# AutoReverseAVR2.net
KiCad netlist of a schematic drawn in Altium Designer
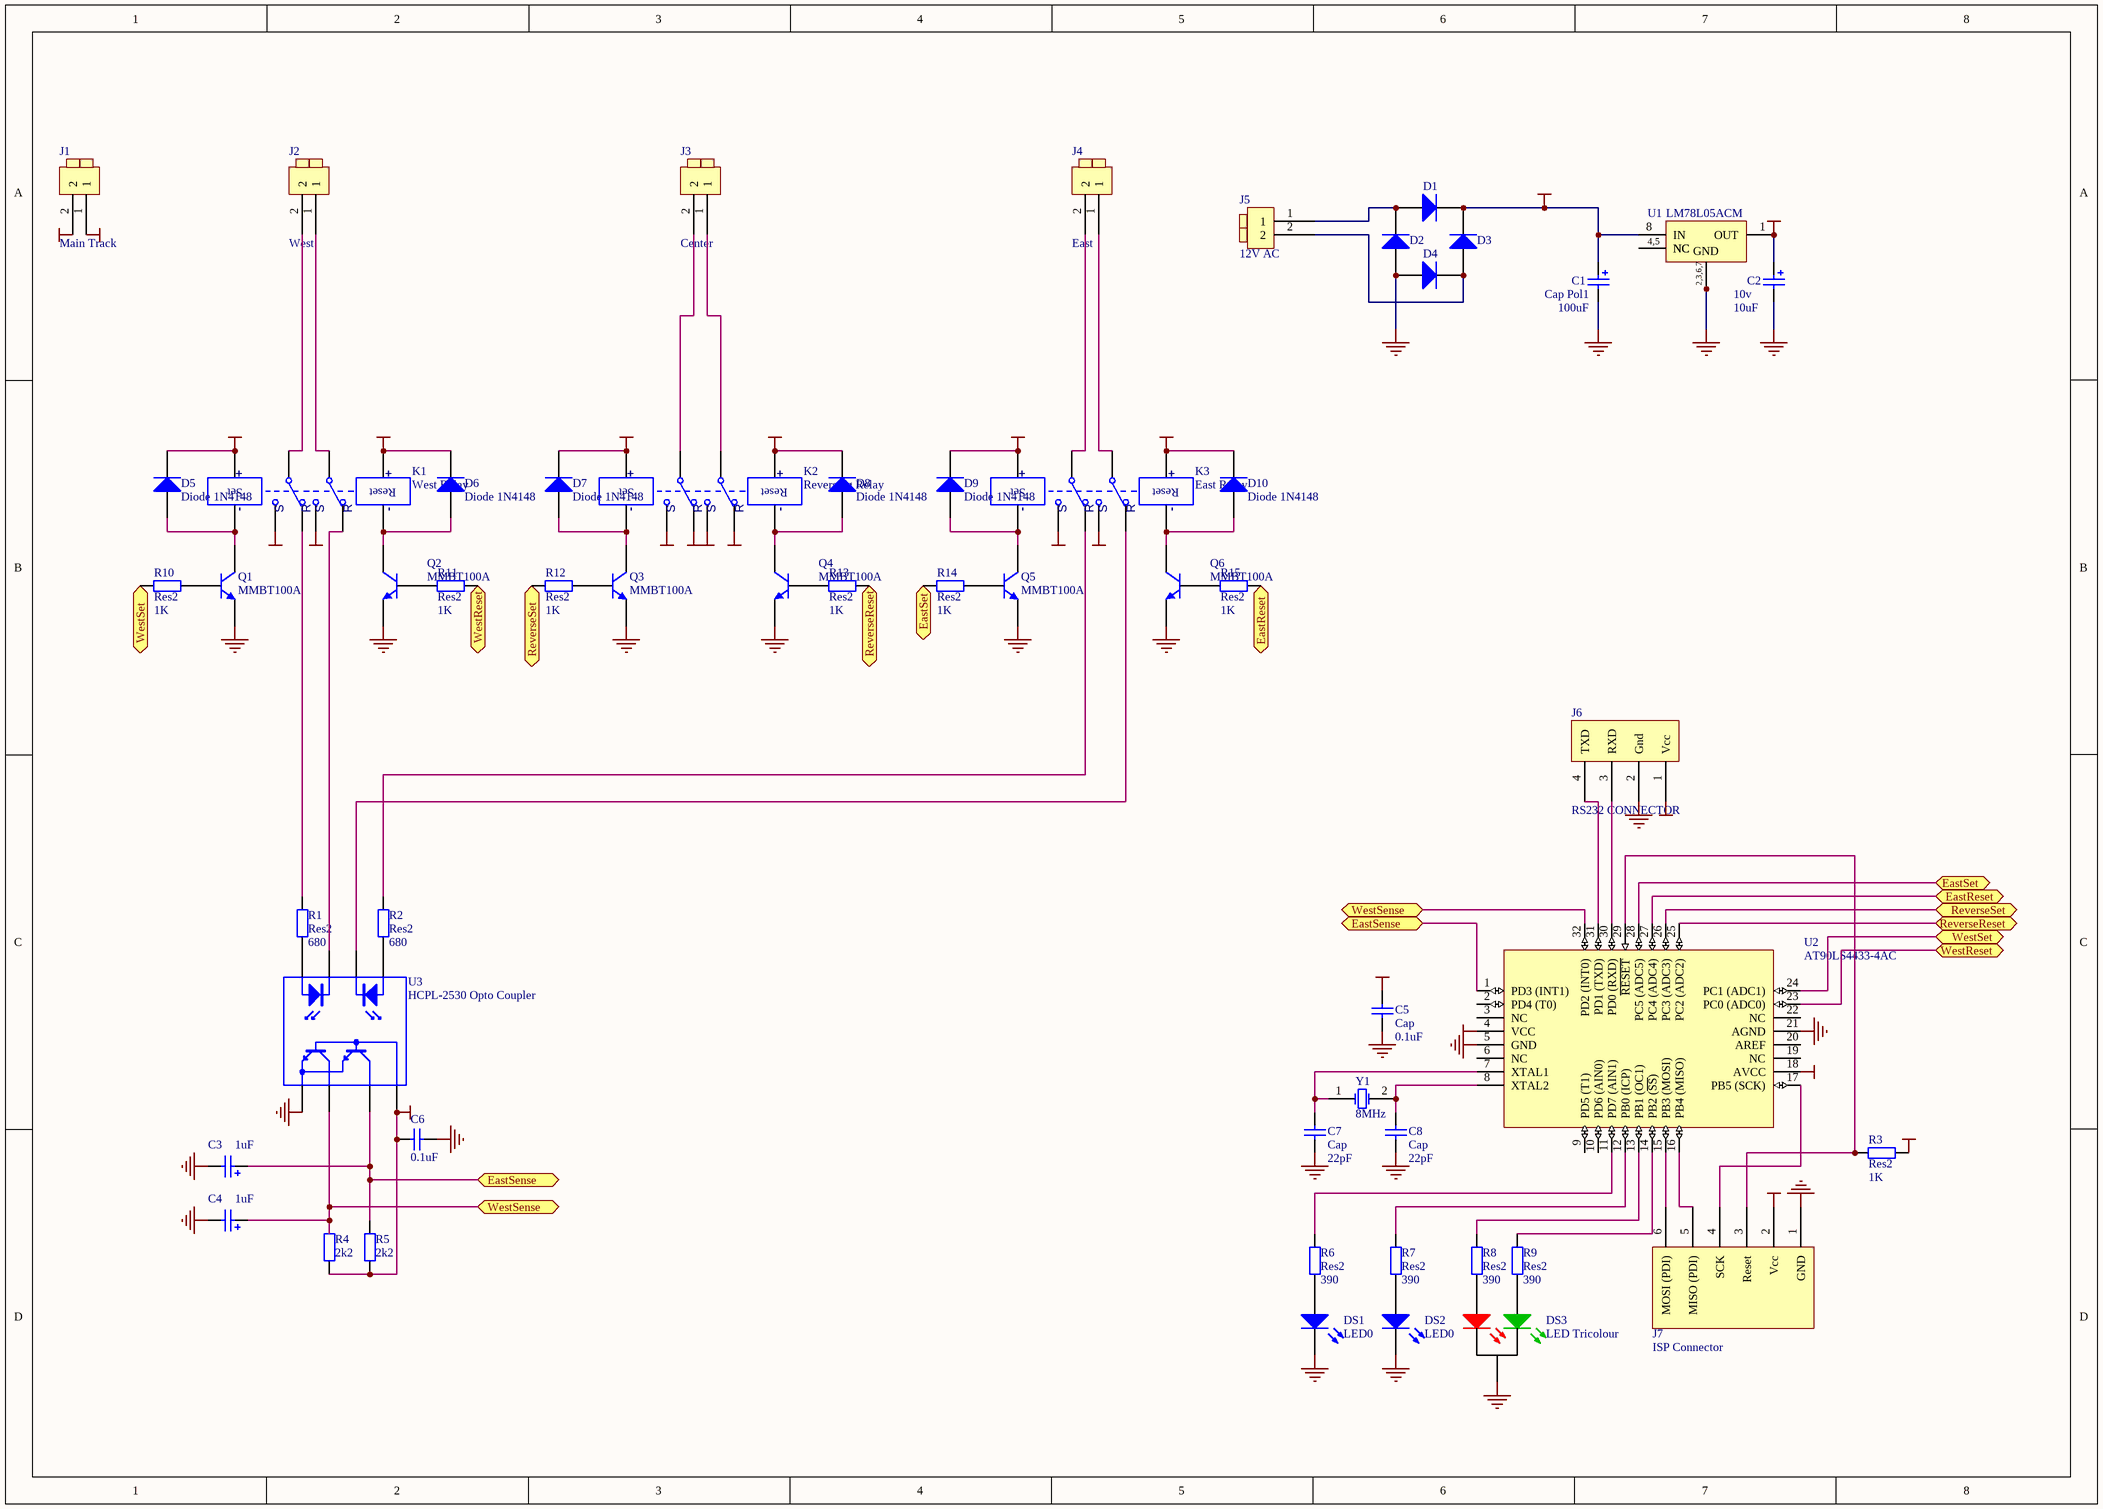
[diagram p0: AutoReverseAVR2.SchDoc]

(export (version "E")
  (design (tool "Eeschema 10.0.6"))
  (components
    (comp (ref "C1")
      (value "Cap Pol1")
      (footprint "CAPPR5-10X10.5")
      (description "Polarized Capacitor (Radial)")
      (fields (field (name "ALTIUM_VALUE") "100uF") (field (name "PUBLISHER") "Altium Limited"))
      (libsource (lib "Miscellaneous Devices") (part "Cap Pol1"))
    )
    (comp (ref "C2")
      (value "10v")
      (footprint "CC3216-1206")
      (description "Polarized Capacitor (Radial)")
      (fields (field (name "ALTIUM_VALUE") "10uF") (field (name "PUBLISHER") "Altium Limited"))
      (libsource (lib "Miscellaneous Devices") (part "Cap Pol1"))
    )
    (comp (ref "C3")
      (value "1uF")
      (footprint "CC3216-1206")
      (description "Polarized Capacitor (Radial)")
      (fields (field (name "Comment") "Cap Pol1") (field (name "PUBLISHER") "Altium Limited"))
      (libsource (lib "Miscellaneous Devices") (part "Cap Pol1"))
    )
    (comp (ref "C4")
      (value "1uF")
      (footprint "CC3216-1206")
      (description "Polarized Capacitor (Radial)")
      (fields (field (name "Comment") "Cap Pol1") (field (name "PUBLISHER") "Altium Limited"))
      (libsource (lib "Miscellaneous Devices") (part "Cap Pol1"))
    )
    (comp (ref "C5")
      (value "Cap")
      (footprint "CC2012-0805")
      (description "Capacitor")
      (fields (field (name "ALTIUM_VALUE") "0.1uF") (field (name "PUBLISHER") "Altium Limited"))
      (libsource (lib "Miscellaneous Devices") (part "Cap"))
    )
    (comp (ref "C6")
      (value "0.1uF")
      (footprint "CC2012-0805")
      (description "Capacitor")
      (fields (field (name "Comment") "Cap") (field (name "PUBLISHER") "Altium Limited"))
      (libsource (lib "Miscellaneous Devices") (part "Cap"))
    )
    (comp (ref "C7")
      (value "Cap")
      (footprint "CC2012-0805")
      (description "Capacitor")
      (fields (field (name "ALTIUM_VALUE") "22pF") (field (name "PUBLISHER") "Altium Limited"))
      (libsource (lib "Miscellaneous Devices") (part "Cap"))
    )
    (comp (ref "C8")
      (value "Cap")
      (footprint "CC2012-0805")
      (description "Capacitor")
      (fields (field (name "ALTIUM_VALUE") "22pF") (field (name "PUBLISHER") "Altium Limited"))
      (libsource (lib "Miscellaneous Devices") (part "Cap"))
    )
    (comp (ref "D1")
      (value "Diode 1N4004")
      (footprint "DIO10.46-5.3x2.8")
      (description "1 Amp General Purpose Rectifier")
      (fields (field (name "PUBLISHER") "Altium Limited"))
      (libsource (lib "Miscellaneous Devices") (part "Diode 1N4004"))
    )
    (comp (ref "D2")
      (value "Diode 1N4004")
      (footprint "DIO10.46-5.3x2.8")
      (description "1 Amp General Purpose Rectifier")
      (fields (field (name "PUBLISHER") "Altium Limited"))
      (libsource (lib "Miscellaneous Devices") (part "Diode 1N4004"))
    )
    (comp (ref "D3")
      (value "Diode 1N4004")
      (footprint "DIO10.46-5.3x2.8")
      (description "1 Amp General Purpose Rectifier")
      (fields (field (name "PUBLISHER") "Altium Limited"))
      (libsource (lib "Miscellaneous Devices") (part "Diode 1N4004"))
    )
    (comp (ref "D4")
      (value "Diode 1N4004")
      (footprint "DIO10.46-5.3x2.8")
      (description "1 Amp General Purpose Rectifier")
      (fields (field (name "PUBLISHER") "Altium Limited"))
      (libsource (lib "Miscellaneous Devices") (part "Diode 1N4004"))
    )
    (comp (ref "D5")
      (value "Diode 1N4148")
      (footprint "DIO7.1-3.9x1.9")
      (description "High Conductance Fast Diode")
      (fields (field (name "PUBLISHER") "Altium Limited"))
      (libsource (lib "Miscellaneous Devices") (part "Diode 1N4148"))
    )
    (comp (ref "D6")
      (value "Diode 1N4148")
      (footprint "DIO7.1-3.9x1.9")
      (description "High Conductance Fast Diode")
      (fields (field (name "PUBLISHER") "Altium Limited"))
      (libsource (lib "Miscellaneous Devices") (part "Diode 1N4148"))
    )
    (comp (ref "D7")
      (value "Diode 1N4148")
      (footprint "DIO7.1-3.9x1.9")
      (description "High Conductance Fast Diode")
      (fields (field (name "PUBLISHER") "Altium Limited"))
      (libsource (lib "Miscellaneous Devices") (part "Diode 1N4148"))
    )
    (comp (ref "D8")
      (value "Diode 1N4148")
      (footprint "DIO7.1-3.9x1.9")
      (description "High Conductance Fast Diode")
      (fields (field (name "PUBLISHER") "Altium Limited"))
      (libsource (lib "Miscellaneous Devices") (part "Diode 1N4148"))
    )
    (comp (ref "D9")
      (value "Diode 1N4148")
      (footprint "DIO7.1-3.9x1.9")
      (description "High Conductance Fast Diode")
      (fields (field (name "PUBLISHER") "Altium Limited"))
      (libsource (lib "Miscellaneous Devices") (part "Diode 1N4148"))
    )
    (comp (ref "D10")
      (value "Diode 1N4148")
      (footprint "DIO7.1-3.9x1.9")
      (description "High Conductance Fast Diode")
      (fields (field (name "PUBLISHER") "Altium Limited"))
      (libsource (lib "Miscellaneous Devices") (part "Diode 1N4148"))
    )
    (comp (ref "DS1")
      (value "LED0")
      (footprint "LED3mm")
      (description "Typical INFRARED GaAs LED")
      (fields (field (name "PUBLISHER") "Altium Limited"))
      (libsource (lib "Miscellaneous Devices") (part "LED0"))
    )
    (comp (ref "DS2")
      (value "LED0")
      (footprint "LED3mm")
      (description "Typical INFRARED GaAs LED")
      (fields (field (name "PUBLISHER") "Altium Limited"))
      (libsource (lib "Miscellaneous Devices") (part "LED0"))
    )
    (comp (ref "DS3")
      (value "LED Tricolour")
      (footprint "LED3mm TriColour")
      (description "Typical Red Green Tri Color LED")
      (fields (field (name "PUBLISHER") "Altium Limited"))
      (libsource (lib "Custom") (part "LED Tricolour"))
    )
    (comp (ref "J1")
      (value "Main Track")
      (footprint "Screw Terminal 2 way 0.2")
      (libsource (lib "Custom") (part "Screw Terminal 2 Way"))
    )
    (comp (ref "J2")
      (value "West")
      (footprint "Screw Terminal 2 way 0.2")
      (libsource (lib "Custom") (part "Screw Terminal 2 Way"))
    )
    (comp (ref "J3")
      (value "Center")
      (footprint "Screw Terminal 2 way 0.2")
      (libsource (lib "Custom") (part "Screw Terminal 2 Way"))
    )
    (comp (ref "J4")
      (value "East")
      (footprint "Screw Terminal 2 way 0.2")
      (libsource (lib "Custom") (part "Screw Terminal 2 Way"))
    )
    (comp (ref "J5")
      (value "12V AC")
      (footprint "Screw Terminal 2 way 0.2")
      (libsource (lib "") (part "Screw Terminal 2 Way_1"))
    )
    (comp (ref "J6")
      (value "RS232 CONNECTOR")
      (footprint "0.1 SIP 4 PIN")
      (libsource (lib "Custom") (part "RS232 CONNECTOR"))
    )
    (comp (ref "J7")
      (value "ISP Connector")
      (footprint "0.1 SIP 6 PIN")
      (libsource (lib "Custom") (part "ISP Connector"))
    )
    (comp (ref "K1")
      (value "West Relay")
      (footprint "DIP-10")
      (description "EA2-5T Dual Coil 5V Latching Relay")
      (fields (field (name "PUBLISHER") "Altium Limited"))
      (libsource (lib "Custom") (part "EA2-5T Dual Coil 5V Latching Relay"))
    )
    (comp (ref "K2")
      (value "Reversing Relay")
      (footprint "DIP-10")
      (description "EA2-5T Dual Coil 5V Latching Relay")
      (fields (field (name "PUBLISHER") "Altium Limited"))
      (libsource (lib "Custom") (part "EA2-5T Dual Coil 5V Latching Relay"))
    )
    (comp (ref "K3")
      (value "East Relay")
      (footprint "DIP-10")
      (description "EA2-5T Dual Coil 5V Latching Relay")
      (fields (field (name "PUBLISHER") "Altium Limited"))
      (libsource (lib "Custom") (part "EA2-5T Dual Coil 5V Latching Relay"))
    )
    (comp (ref "Q1")
      (value "MMBT100A")
      (footprint "SO-G3")
      (description "General Purpose Amplifier NPN Silicon")
      (fields (field (name "PUBLISHER") "Altium Limited"))
      (libsource (lib "Custom") (part "MMBT100A"))
    )
    (comp (ref "Q2")
      (value "MMBT100A")
      (footprint "SO-G3")
      (description "General Purpose Amplifier NPN Silicon")
      (fields (field (name "PUBLISHER") "Altium Limited"))
      (libsource (lib "Custom") (part "MMBT100A"))
    )
    (comp (ref "Q3")
      (value "MMBT100A")
      (footprint "SO-G3")
      (description "General Purpose Amplifier NPN Silicon")
      (fields (field (name "PUBLISHER") "Altium Limited"))
      (libsource (lib "Custom") (part "MMBT100A"))
    )
    (comp (ref "Q4")
      (value "MMBT100A")
      (footprint "SO-G3")
      (description "General Purpose Amplifier NPN Silicon")
      (fields (field (name "PUBLISHER") "Altium Limited"))
      (libsource (lib "Custom") (part "MMBT100A"))
    )
    (comp (ref "Q5")
      (value "MMBT100A")
      (footprint "SO-G3")
      (description "General Purpose Amplifier NPN Silicon")
      (fields (field (name "PUBLISHER") "Altium Limited"))
      (libsource (lib "Custom") (part "MMBT100A"))
    )
    (comp (ref "Q6")
      (value "MMBT100A")
      (footprint "SO-G3")
      (description "General Purpose Amplifier NPN Silicon")
      (fields (field (name "PUBLISHER") "Altium Limited"))
      (libsource (lib "Custom") (part "MMBT100A"))
    )
    (comp (ref "R1")
      (value "Res2")
      (footprint "CR2012-0805")
      (description "Resistor")
      (fields (field (name "ALTIUM_VALUE") "680") (field (name "PUBLISHER") "Altium Limited"))
      (libsource (lib "Miscellaneous Devices") (part "Res2"))
    )
    (comp (ref "R2")
      (value "Res2")
      (footprint "CR2012-0805")
      (description "Resistor")
      (fields (field (name "ALTIUM_VALUE") "680") (field (name "PUBLISHER") "Altium Limited"))
      (libsource (lib "Miscellaneous Devices") (part "Res2"))
    )
    (comp (ref "R3")
      (value "Res2")
      (footprint "CR2012-0805")
      (description "Resistor")
      (fields (field (name "ALTIUM_VALUE") "1K") (field (name "PUBLISHER") "Altium Limited"))
      (libsource (lib "") (part "Res2_3"))
    )
    (comp (ref "R4")
      (value "2k2")
      (footprint "CR2012-0805")
      (description "Resistor")
      (fields (field (name "Comment") "Res2") (field (name "PUBLISHER") "Altium Limited"))
      (libsource (lib "") (part "Res2_2"))
    )
    (comp (ref "R5")
      (value "2k2")
      (footprint "CR2012-0805")
      (description "Resistor")
      (fields (field (name "Comment") "Res2") (field (name "PUBLISHER") "Altium Limited"))
      (libsource (lib "") (part "Res2_2"))
    )
    (comp (ref "R6")
      (value "Res2")
      (footprint "CR2012-0805")
      (description "Resistor")
      (fields (field (name "ALTIUM_VALUE") "390") (field (name "PUBLISHER") "Altium Limited"))
      (libsource (lib "Miscellaneous Devices") (part "Res2"))
    )
    (comp (ref "R7")
      (value "Res2")
      (footprint "CR2012-0805")
      (description "Resistor")
      (fields (field (name "ALTIUM_VALUE") "390") (field (name "PUBLISHER") "Altium Limited"))
      (libsource (lib "Miscellaneous Devices") (part "Res2"))
    )
    (comp (ref "R8")
      (value "Res2")
      (footprint "CR2012-0805")
      (description "Resistor")
      (fields (field (name "ALTIUM_VALUE") "390") (field (name "PUBLISHER") "Altium Limited"))
      (libsource (lib "Miscellaneous Devices") (part "Res2"))
    )
    (comp (ref "R9")
      (value "Res2")
      (footprint "CR2012-0805")
      (description "Resistor")
      (fields (field (name "ALTIUM_VALUE") "390") (field (name "PUBLISHER") "Altium Limited"))
      (libsource (lib "Miscellaneous Devices") (part "Res2"))
    )
    (comp (ref "R10")
      (value "Res2")
      (footprint "CR2012-0805")
      (description "Resistor")
      (fields (field (name "ALTIUM_VALUE") "1K") (field (name "PUBLISHER") "Altium Limited"))
      (libsource (lib "") (part "Res2_2"))
    )
    (comp (ref "R11")
      (value "Res2")
      (footprint "CR2012-0805")
      (description "Resistor")
      (fields (field (name "ALTIUM_VALUE") "1K") (field (name "PUBLISHER") "Altium Limited"))
      (libsource (lib "") (part "Res2_1"))
    )
    (comp (ref "R12")
      (value "Res2")
      (footprint "CR2012-0805")
      (description "Resistor")
      (fields (field (name "ALTIUM_VALUE") "1K") (field (name "PUBLISHER") "Altium Limited"))
      (libsource (lib "") (part "Res2_2"))
    )
    (comp (ref "R13")
      (value "Res2")
      (footprint "CR2012-0805")
      (description "Resistor")
      (fields (field (name "ALTIUM_VALUE") "1K") (field (name "PUBLISHER") "Altium Limited"))
      (libsource (lib "") (part "Res2_1"))
    )
    (comp (ref "R14")
      (value "Res2")
      (footprint "CR2012-0805")
      (description "Resistor")
      (fields (field (name "ALTIUM_VALUE") "1K") (field (name "PUBLISHER") "Altium Limited"))
      (libsource (lib "") (part "Res2_2"))
    )
    (comp (ref "R15")
      (value "Res2")
      (footprint "CR2012-0805")
      (description "Resistor")
      (fields (field (name "ALTIUM_VALUE") "1K") (field (name "PUBLISHER") "Altium Limited"))
      (libsource (lib "") (part "Res2_1"))
    )
    (comp (ref "U1")
      (value "LM78L05ACM")
      (footprint "M08A")
      (description "3-Terminal Positive Regulator")
      (fields (field (name "PUBLISHER") "Altium Limited"))
      (libsource (lib "NSC Power Mgt Voltage Regulator") (part "LM78L05ACM"))
    )
    (comp (ref "U2")
      (value "AT90LS4433-4AC")
      (footprint "32A")
      (description "8-Bit AVR Microcontroller with 4K Bytes of In-System Programmable Flash Memory")
      (fields (field (name "PUBLISHER") "Altium Limited"))
      (libsource (lib "Custom") (part "AT90LS4433-4AC"))
    )
    (comp (ref "U3")
      (value "HCPL-2530 Opto Coupler")
      (footprint "8P3")
      (libsource (lib "Custom") (part "HCPL-2530"))
    )
    (comp (ref "Y1")
      (value "8MHz")
      (footprint "RAD-0.2")
      (description "Crystal Oscillator")
      (fields (field (name "PUBLISHER") "Altium Limited"))
      (libsource (lib "Miscellaneous Devices") (part "XTAL"))
    )
  )
  (nets
    (net (code "1") (name "/EastReset") (class "Default")
      (node (ref "R15") (pin "2") (pinfunction "2_2") (pintype "passive"))
      (node (ref "U2") (pin "27") (pinfunction "PC4_(ADC4)_27") (pintype "bidirectional"))
    )
    (net (code "2") (name "/EastSense") (class "Default")
      (node (ref "C3") (pin "1") (pinfunction "1_1") (pintype "passive"))
      (node (ref "R5") (pin "1") (pinfunction "1_1") (pintype "passive"))
      (node (ref "U2") (pin "1") (pinfunction "PD3_(INT1)_1") (pintype "bidirectional"))
      (node (ref "U3") (pin "7") (pinfunction "C_7") (pintype "passive"))
    )
    (net (code "3") (name "/EastSet") (class "Default")
      (node (ref "R14") (pin "2") (pinfunction "2_2") (pintype "passive"))
      (node (ref "U2") (pin "28") (pinfunction "PC5_(ADC5)_28") (pintype "bidirectional"))
    )
    (net (code "4") (name "/ReverseReset") (class "Default")
      (node (ref "R13") (pin "2") (pinfunction "2_2") (pintype "passive"))
      (node (ref "U2") (pin "25") (pinfunction "PC2_(ADC2)_25") (pintype "bidirectional"))
    )
    (net (code "5") (name "/ReverseSet") (class "Default")
      (node (ref "R12") (pin "2") (pinfunction "2_2") (pintype "passive"))
      (node (ref "U2") (pin "26") (pinfunction "PC3_(ADC3)_26") (pintype "bidirectional"))
    )
    (net (code "6") (name "/WestReset") (class "Default")
      (node (ref "R11") (pin "2") (pinfunction "2_2") (pintype "passive"))
      (node (ref "U2") (pin "23") (pinfunction "PC0_(ADC0)_23") (pintype "bidirectional"))
    )
    (net (code "7") (name "/WestSense") (class "Default")
      (node (ref "C4") (pin "1") (pinfunction "1_1") (pintype "passive"))
      (node (ref "R4") (pin "1") (pinfunction "1_1") (pintype "passive"))
      (node (ref "U2") (pin "32") (pinfunction "PD2_(INT0)_32") (pintype "bidirectional"))
      (node (ref "U3") (pin "6") (pinfunction "C_6") (pintype "passive"))
    )
    (net (code "8") (name "/WestSet") (class "Default")
      (node (ref "R10") (pin "2") (pinfunction "2_2") (pintype "passive"))
      (node (ref "U2") (pin "24") (pinfunction "PC1_(ADC1)_24") (pintype "bidirectional"))
    )
    (net (code "9") (name "A") (class "Default")
      (node (ref "J1") (pin "2") (pinfunction "2_2") (pintype "passive"))
      (node (ref "K1") (pin "7") (pinfunction "S_7") (pintype "passive"))
      (node (ref "K2") (pin "2") (pinfunction "R_2") (pintype "passive"))
      (node (ref "K2") (pin "7") (pinfunction "S_7") (pintype "passive"))
      (node (ref "K3") (pin "7") (pinfunction "S_7") (pintype "passive"))
    )
    (net (code "10") (name "B") (class "Default")
      (node (ref "J1") (pin "1") (pinfunction "1_1") (pintype "passive"))
      (node (ref "K1") (pin "4") (pinfunction "S_4") (pintype "passive"))
      (node (ref "K2") (pin "4") (pinfunction "S_4") (pintype "passive"))
      (node (ref "K2") (pin "9") (pinfunction "R_9") (pintype "passive"))
      (node (ref "K3") (pin "4") (pinfunction "S_4") (pintype "passive"))
    )
    (net (code "11") (name "GND") (class "Default")
      (node (ref "C1") (pin "2") (pinfunction "2_2") (pintype "passive"))
      (node (ref "C2") (pin "2") (pinfunction "2_2") (pintype "passive"))
      (node (ref "C3") (pin "2") (pinfunction "2_2") (pintype "passive"))
      (node (ref "C4") (pin "2") (pinfunction "2_2") (pintype "passive"))
      (node (ref "C5") (pin "1") (pinfunction "1_1") (pintype "passive"))
      (node (ref "C6") (pin "2") (pinfunction "2_2") (pintype "passive"))
      (node (ref "C7") (pin "1") (pinfunction "1_1") (pintype "passive"))
      (node (ref "C8") (pin "1") (pinfunction "1_1") (pintype "passive"))
      (node (ref "D2") (pin "1") (pinfunction "A_1") (pintype "passive"))
      (node (ref "D4") (pin "1") (pinfunction "A_1") (pintype "passive"))
      (node (ref "DS1") (pin "2") (pinfunction "K_2") (pintype "passive"))
      (node (ref "DS2") (pin "2") (pinfunction "K_2") (pintype "passive"))
      (node (ref "DS3") (pin "2") (pinfunction "K_2") (pintype "passive"))
      (node (ref "J6") (pin "2") (pinfunction "Gnd_2") (pintype "passive"))
      (node (ref "J7") (pin "1") (pinfunction "GND_1") (pintype "passive"))
      (node (ref "Q1") (pin "2") (pinfunction "E_2") (pintype "passive"))
      (node (ref "Q2") (pin "2") (pinfunction "E_2") (pintype "passive"))
      (node (ref "Q3") (pin "2") (pinfunction "E_2") (pintype "passive"))
      (node (ref "Q4") (pin "2") (pinfunction "E_2") (pintype "passive"))
      (node (ref "Q5") (pin "2") (pinfunction "E_2") (pintype "passive"))
      (node (ref "Q6") (pin "2") (pinfunction "E_2") (pintype "passive"))
      (node (ref "U1") (pin "2") (pinfunction "GND_2") (pintype "power_in"))
      (node (ref "U1") (pin "3") (pinfunction "GND_3") (pintype "power_in"))
      (node (ref "U1") (pin "6") (pinfunction "GND_6") (pintype "power_in"))
      (node (ref "U1") (pin "7") (pinfunction "GND_7") (pintype "power_in"))
      (node (ref "U2") (pin "21") (pinfunction "AGND_21") (pintype "power_in"))
      (node (ref "U2") (pin "5") (pinfunction "GND_5") (pintype "power_in"))
      (node (ref "U3") (pin "5") (pinfunction "E_5") (pintype "passive"))
    )
    (net (code "12") (name "Net-(D1-A)") (class "Default")
      (node (ref "D1") (pin "1") (pinfunction "A_1") (pintype "passive"))
      (node (ref "D2") (pin "2") (pinfunction "K_2") (pintype "passive"))
      (node (ref "J5") (pin "1") (pinfunction "1_1") (pintype "passive"))
    )
    (net (code "13") (name "Net-(D3-A)") (class "Default")
      (node (ref "D3") (pin "1") (pinfunction "A_1") (pintype "passive"))
      (node (ref "D4") (pin "2") (pinfunction "K_2") (pintype "passive"))
      (node (ref "J5") (pin "2") (pinfunction "2_2") (pintype "passive"))
    )
    (net (code "14") (name "Net-(D5-A)") (class "Default")
      (node (ref "D5") (pin "1") (pinfunction "A_1") (pintype "passive"))
      (node (ref "K1") (pin "5") (pintype "passive"))
      (node (ref "Q1") (pin "3") (pinfunction "C_3") (pintype "passive"))
    )
    (net (code "15") (name "Net-(D6-A)") (class "Default")
      (node (ref "D6") (pin "1") (pinfunction "A_1") (pintype "passive"))
      (node (ref "K1") (pin "6") (pintype "passive"))
      (node (ref "Q2") (pin "3") (pinfunction "C_3") (pintype "passive"))
    )
    (net (code "16") (name "Net-(D7-A)") (class "Default")
      (node (ref "D7") (pin "1") (pinfunction "A_1") (pintype "passive"))
      (node (ref "K2") (pin "5") (pintype "passive"))
      (node (ref "Q3") (pin "3") (pinfunction "C_3") (pintype "passive"))
    )
    (net (code "17") (name "Net-(D8-A)") (class "Default")
      (node (ref "D8") (pin "1") (pinfunction "A_1") (pintype "passive"))
      (node (ref "K2") (pin "6") (pintype "passive"))
      (node (ref "Q4") (pin "3") (pinfunction "C_3") (pintype "passive"))
    )
    (net (code "18") (name "Net-(D9-A)") (class "Default")
      (node (ref "D9") (pin "1") (pinfunction "A_1") (pintype "passive"))
      (node (ref "K3") (pin "5") (pintype "passive"))
      (node (ref "Q5") (pin "3") (pinfunction "C_3") (pintype "passive"))
    )
    (net (code "19") (name "Net-(D10-A)") (class "Default")
      (node (ref "D10") (pin "1") (pinfunction "A_1") (pintype "passive"))
      (node (ref "K3") (pin "6") (pintype "passive"))
      (node (ref "Q6") (pin "3") (pinfunction "C_3") (pintype "passive"))
    )
    (net (code "20") (name "Net-(DS1-A)") (class "Default")
      (node (ref "DS1") (pin "1") (pinfunction "A_1") (pintype "passive"))
      (node (ref "R6") (pin "1") (pinfunction "1_1") (pintype "passive"))
    )
    (net (code "21") (name "Net-(DS2-A)") (class "Default")
      (node (ref "DS2") (pin "1") (pinfunction "A_1") (pintype "passive"))
      (node (ref "R7") (pin "1") (pinfunction "1_1") (pintype "passive"))
    )
    (net (code "22") (name "Net-(DS3-Ag)") (class "Default")
      (node (ref "DS3") (pin "1") (pinfunction "Ag_1") (pintype "passive"))
      (node (ref "R9") (pin "1") (pinfunction "1_1") (pintype "passive"))
    )
    (net (code "23") (name "Net-(DS3-Ar)") (class "Default")
      (node (ref "DS3") (pin "3") (pinfunction "Ar_3") (pintype "passive"))
      (node (ref "R8") (pin "1") (pinfunction "1_1") (pintype "passive"))
    )
    (net (code "24") (name "Net-(J2-Pad1)") (class "Default")
      (node (ref "J2") (pin "1") (pinfunction "1_1") (pintype "passive"))
      (node (ref "K1") (pin "3") (pinfunction "3_3") (pintype "passive"))
    )
    (net (code "25") (name "Net-(J2-Pad2)") (class "Default")
      (node (ref "J2") (pin "2") (pinfunction "2_2") (pintype "passive"))
      (node (ref "K1") (pin "8") (pinfunction "8_8") (pintype "passive"))
    )
    (net (code "26") (name "Net-(J3-Pad1)") (class "Default")
      (node (ref "J3") (pin "1") (pinfunction "1_1") (pintype "passive"))
      (node (ref "K2") (pin "3") (pinfunction "3_3") (pintype "passive"))
    )
    (net (code "27") (name "Net-(J3-Pad2)") (class "Default")
      (node (ref "J3") (pin "2") (pinfunction "2_2") (pintype "passive"))
      (node (ref "K2") (pin "8") (pinfunction "8_8") (pintype "passive"))
    )
    (net (code "28") (name "Net-(J4-Pad1)") (class "Default")
      (node (ref "J4") (pin "1") (pinfunction "1_1") (pintype "passive"))
      (node (ref "K3") (pin "3") (pinfunction "3_3") (pintype "passive"))
    )
    (net (code "29") (name "Net-(J4-Pad2)") (class "Default")
      (node (ref "J4") (pin "2") (pinfunction "2_2") (pintype "passive"))
      (node (ref "K3") (pin "8") (pinfunction "8_8") (pintype "passive"))
    )
    (net (code "30") (name "Net-(J6-RXD)") (class "Default")
      (node (ref "J6") (pin "3") (pinfunction "RXD_3") (pintype "passive"))
      (node (ref "U2") (pin "30") (pinfunction "PD0_(RXD)_30") (pintype "bidirectional"))
    )
    (net (code "31") (name "Net-(J6-TXD)") (class "Default")
      (node (ref "J6") (pin "4") (pinfunction "TXD_4") (pintype "passive"))
      (node (ref "U2") (pin "31") (pinfunction "PD1_(TXD)_31") (pintype "bidirectional"))
    )
    (net (code "32") (name "Net-(J7-MISO_(PDI))") (class "Default")
      (node (ref "J7") (pin "5") (pinfunction "MISO_(PDI)_5") (pintype "passive"))
      (node (ref "U2") (pin "16") (pinfunction "PB4_(MISO)_16") (pintype "bidirectional"))
    )
    (net (code "33") (name "Net-(J7-MOSI_(PDI))") (class "Default")
      (node (ref "J7") (pin "6") (pinfunction "MOSI_(PDI)_6") (pintype "passive"))
      (node (ref "U2") (pin "15") (pinfunction "PB3_(MOSI)_15") (pintype "bidirectional"))
    )
    (net (code "34") (name "Net-(J7-Reset)") (class "Default")
      (node (ref "J7") (pin "3") (pinfunction "Reset_3") (pintype "passive"))
      (node (ref "R3") (pin "2") (pinfunction "2_2") (pintype "passive"))
      (node (ref "U2") (pin "29") (pinfunction "~{RESET}_29") (pintype "input"))
    )
    (net (code "35") (name "Net-(J7-SCK)") (class "Default")
      (node (ref "J7") (pin "4") (pinfunction "SCK_4") (pintype "passive"))
      (node (ref "U2") (pin "17") (pinfunction "PB5_(SCK)_17") (pintype "bidirectional"))
    )
    (net (code "36") (name "Net-(K1-R-Pad2)") (class "Default")
      (node (ref "K1") (pin "2") (pinfunction "R_2") (pintype "passive"))
      (node (ref "U3") (pin "3") (pinfunction "K_3") (pintype "passive"))
    )
    (net (code "37") (name "Net-(K1-R-Pad9)") (class "Default")
      (node (ref "K1") (pin "9") (pinfunction "R_9") (pintype "passive"))
      (node (ref "R1") (pin "2") (pinfunction "2_2") (pintype "passive"))
    )
    (net (code "38") (name "Net-(K3-R-Pad2)") (class "Default")
      (node (ref "K3") (pin "2") (pinfunction "R_2") (pintype "passive"))
      (node (ref "U3") (pin "2") (pinfunction "K_2") (pintype "passive"))
    )
    (net (code "39") (name "Net-(K3-R-Pad9)") (class "Default")
      (node (ref "K3") (pin "9") (pinfunction "R_9") (pintype "passive"))
      (node (ref "R2") (pin "2") (pinfunction "2_2") (pintype "passive"))
    )
    (net (code "40") (name "Net-(Q1-B)") (class "Default")
      (node (ref "Q1") (pin "1") (pinfunction "B_1") (pintype "passive"))
      (node (ref "R10") (pin "1") (pinfunction "1_1") (pintype "passive"))
    )
    (net (code "41") (name "Net-(Q2-B)") (class "Default")
      (node (ref "Q2") (pin "1") (pinfunction "B_1") (pintype "passive"))
      (node (ref "R11") (pin "1") (pinfunction "1_1") (pintype "passive"))
    )
    (net (code "42") (name "Net-(Q3-B)") (class "Default")
      (node (ref "Q3") (pin "1") (pinfunction "B_1") (pintype "passive"))
      (node (ref "R12") (pin "1") (pinfunction "1_1") (pintype "passive"))
    )
    (net (code "43") (name "Net-(Q4-B)") (class "Default")
      (node (ref "Q4") (pin "1") (pinfunction "B_1") (pintype "passive"))
      (node (ref "R13") (pin "1") (pinfunction "1_1") (pintype "passive"))
    )
    (net (code "44") (name "Net-(Q5-B)") (class "Default")
      (node (ref "Q5") (pin "1") (pinfunction "B_1") (pintype "passive"))
      (node (ref "R14") (pin "1") (pinfunction "1_1") (pintype "passive"))
    )
    (net (code "45") (name "Net-(Q6-B)") (class "Default")
      (node (ref "Q6") (pin "1") (pinfunction "B_1") (pintype "passive"))
      (node (ref "R15") (pin "1") (pinfunction "1_1") (pintype "passive"))
    )
    (net (code "46") (name "Net-(R1-Pad1)") (class "Default")
      (node (ref "R1") (pin "1") (pinfunction "1_1") (pintype "passive"))
      (node (ref "U3") (pin "4") (pinfunction "A_4") (pintype "passive"))
    )
    (net (code "47") (name "Net-(R2-Pad1)") (class "Default")
      (node (ref "R2") (pin "1") (pinfunction "1_1") (pintype "passive"))
      (node (ref "U3") (pin "1") (pinfunction "A_1") (pintype "passive"))
    )
    (net (code "48") (name "Net-(U1-NC-Pad4)") (class "Default")
      (node (ref "U1") (pin "4") (pinfunction "NC_4") (pintype "passive"))
      (node (ref "U1") (pin "5") (pinfunction "NC_5") (pintype "passive"))
    )
    (net (code "49") (name "Net-(U2-PB0_(ICP))") (class "Default")
      (node (ref "R7") (pin "2") (pinfunction "2_2") (pintype "passive"))
      (node (ref "U2") (pin "12") (pinfunction "PB0_(ICP)_12") (pintype "bidirectional"))
    )
    (net (code "50") (name "Net-(U2-PB1_(OC1))") (class "Default")
      (node (ref "R8") (pin "2") (pinfunction "2_2") (pintype "passive"))
      (node (ref "U2") (pin "13") (pinfunction "PB1_(OC1)_13") (pintype "bidirectional"))
    )
    (net (code "51") (name "Net-(U2-PB2_(~{SS}))") (class "Default")
      (node (ref "R9") (pin "2") (pinfunction "2_2") (pintype "passive"))
      (node (ref "U2") (pin "14") (pinfunction "PB2_(~{SS})_14") (pintype "bidirectional"))
    )
    (net (code "52") (name "Net-(U2-PD7_(AIN1))") (class "Default")
      (node (ref "R6") (pin "2") (pinfunction "2_2") (pintype "passive"))
      (node (ref "U2") (pin "11") (pinfunction "PD7_(AIN1)_11") (pintype "bidirectional"))
    )
    (net (code "53") (name "Net-(U2-XTAL1)") (class "Default")
      (node (ref "C7") (pin "2") (pinfunction "2_2") (pintype "passive"))
      (node (ref "U2") (pin "7") (pinfunction "XTAL1_7") (pintype "passive"))
      (node (ref "Y1") (pin "1") (pinfunction "OSC1_1") (pintype "passive"))
    )
    (net (code "54") (name "Net-(U2-XTAL2)") (class "Default")
      (node (ref "C8") (pin "2") (pinfunction "2_2") (pintype "passive"))
      (node (ref "U2") (pin "8") (pinfunction "XTAL2_8") (pintype "passive"))
      (node (ref "Y1") (pin "2") (pinfunction "OSC2_2") (pintype "passive"))
    )
    (net (code "55") (name "VCC") (class "Default")
      (node (ref "C2") (pin "1") (pinfunction "1_1") (pintype "passive"))
      (node (ref "C5") (pin "2") (pinfunction "2_2") (pintype "passive"))
      (node (ref "C6") (pin "1") (pinfunction "1_1") (pintype "passive"))
      (node (ref "J6") (pin "1") (pinfunction "Vcc_1") (pintype "passive"))
      (node (ref "J7") (pin "2") (pinfunction "Vcc_2") (pintype "passive"))
      (node (ref "R3") (pin "1") (pinfunction "1_1") (pintype "passive"))
      (node (ref "R4") (pin "2") (pinfunction "2_2") (pintype "passive"))
      (node (ref "R5") (pin "2") (pinfunction "2_2") (pintype "passive"))
      (node (ref "U1") (pin "1") (pinfunction "OUT_1") (pintype "power_in"))
      (node (ref "U2") (pin "18") (pinfunction "AVCC_18") (pintype "power_in"))
      (node (ref "U2") (pin "4") (pinfunction "VCC_4") (pintype "power_in"))
      (node (ref "U3") (pin "8") (pinfunction "E_8") (pintype "passive"))
    )
    (net (code "56") (name "Vdd") (class "Default")
      (node (ref "C1") (pin "1") (pinfunction "1_1") (pintype "passive"))
      (node (ref "D1") (pin "2") (pinfunction "K_2") (pintype "passive"))
      (node (ref "D10") (pin "2") (pinfunction "K_2") (pintype "passive"))
      (node (ref "D3") (pin "2") (pinfunction "K_2") (pintype "passive"))
      (node (ref "D5") (pin "2") (pinfunction "K_2") (pintype "passive"))
      (node (ref "D6") (pin "2") (pinfunction "K_2") (pintype "passive"))
      (node (ref "D7") (pin "2") (pinfunction "K_2") (pintype "passive"))
      (node (ref "D8") (pin "2") (pinfunction "K_2") (pintype "passive"))
      (node (ref "D9") (pin "2") (pinfunction "K_2") (pintype "passive"))
      (node (ref "K1") (pin "1") (pintype "passive"))
      (node (ref "K1") (pin "10") (pintype "passive"))
      (node (ref "K2") (pin "1") (pintype "passive"))
      (node (ref "K2") (pin "10") (pintype "passive"))
      (node (ref "K3") (pin "1") (pintype "passive"))
      (node (ref "K3") (pin "10") (pintype "passive"))
      (node (ref "U1") (pin "8") (pinfunction "IN_8") (pintype "power_in"))
    )
    (net (code "57") (name "unconnected-(U2-AREF-Pad20)") (class "Default")
      (node (ref "U2") (pin "20") (pinfunction "AREF_20") (pintype "passive"))
    )
    (net (code "58") (name "unconnected-(U2-NC-Pad3)") (class "Default")
      (node (ref "U2") (pin "3") (pinfunction "NC_3") (pintype "passive"))
    )
    (net (code "59") (name "unconnected-(U2-NC-Pad6)") (class "Default")
      (node (ref "U2") (pin "6") (pinfunction "NC_6") (pintype "passive"))
    )
    (net (code "60") (name "unconnected-(U2-NC-Pad19)") (class "Default")
      (node (ref "U2") (pin "19") (pinfunction "NC_19") (pintype "passive"))
    )
    (net (code "61") (name "unconnected-(U2-NC-Pad22)") (class "Default")
      (node (ref "U2") (pin "22") (pinfunction "NC_22") (pintype "passive"))
    )
    (net (code "62") (name "unconnected-(U2-PD4_(T0)-Pad2)") (class "Default")
      (node (ref "U2") (pin "2") (pinfunction "PD4_(T0)_2") (pintype "bidirectional"))
    )
    (net (code "63") (name "unconnected-(U2-PD5_(T1)-Pad9)") (class "Default")
      (node (ref "U2") (pin "9") (pinfunction "PD5_(T1)_9") (pintype "bidirectional"))
    )
    (net (code "64") (name "unconnected-(U2-PD6_(AIN0)-Pad10)") (class "Default")
      (node (ref "U2") (pin "10") (pinfunction "PD6_(AIN0)_10") (pintype "bidirectional"))
    )
  )
)
